# synth-zodiac-scorpio-kbd-mcu.net
KiCad netlist of a schematic drawn in EAGLE
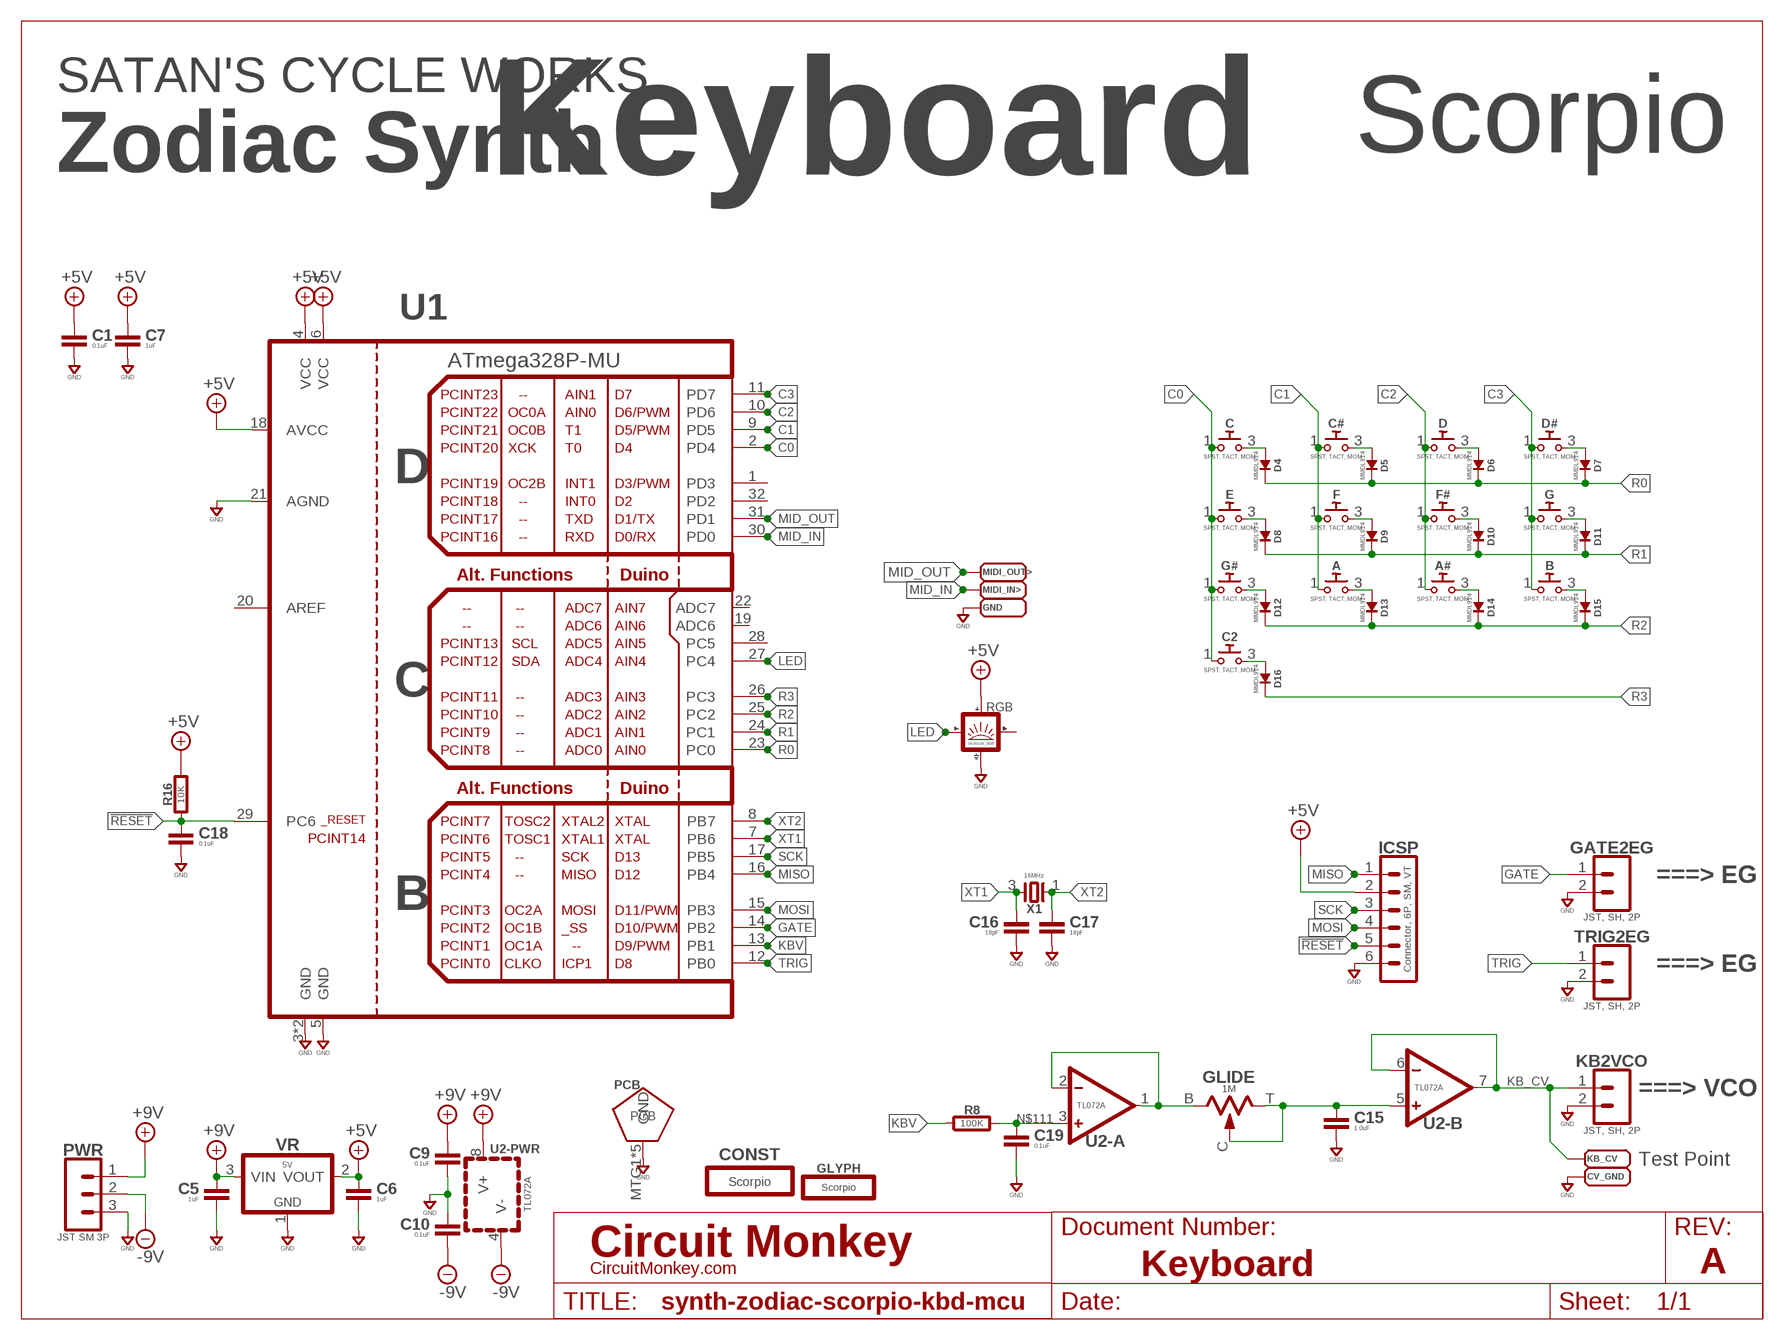
[diagram p0: schematic, sheet 1]

(export (version "E")
  (design (tool "Eeschema 10.0.6"))
  (components
    (comp (ref "A")
      (value "SPST, TACT, MOM")
      (footprint "eagle-import:B3FS-BACKMOUNT")
      (fields (field (name "MFR") "CK") (field (name "MPN") "B3FS"))
      (libsource (lib "eagle-import") (part "PUSHBTN-MOMB3FS-BLIND"))
    )
    (comp (ref "A#")
      (value "SPST, TACT, MOM")
      (footprint "eagle-import:B3FS-BACKMOUNT")
      (fields (field (name "MFR") "CK") (field (name "MPN") "B3FS"))
      (libsource (lib "eagle-import") (part "PUSHBTN-MOMB3FS-BLIND"))
    )
    (comp (ref "B")
      (value "SPST, TACT, MOM")
      (footprint "eagle-import:B3FS-BACKMOUNT")
      (fields (field (name "MFR") "CK") (field (name "MPN") "B3FS"))
      (libsource (lib "eagle-import") (part "PUSHBTN-MOMB3FS-BLIND"))
    )
    (comp (ref "C")
      (value "SPST, TACT, MOM")
      (footprint "eagle-import:B3FS-BACKMOUNT")
      (fields (field (name "MFR") "CK") (field (name "MPN") "B3FS"))
      (libsource (lib "eagle-import") (part "PUSHBTN-MOMB3FS-BLIND"))
    )
    (comp (ref "C#")
      (value "SPST, TACT, MOM")
      (footprint "eagle-import:B3FS-BACKMOUNT")
      (fields (field (name "MFR") "CK") (field (name "MPN") "B3FS"))
      (libsource (lib "eagle-import") (part "PUSHBTN-MOMB3FS-BLIND"))
    )
    (comp (ref "C1")
      (value "0.1uF")
      (footprint "eagle-import:0603-CAP")
      (libsource (lib "eagle-import") (part "CAPACITOR0603"))
    )
    (comp (ref "C2")
      (value "SPST, TACT, MOM")
      (footprint "eagle-import:B3FS-BACKMOUNT")
      (fields (field (name "MFR") "CK") (field (name "MPN") "B3FS"))
      (libsource (lib "eagle-import") (part "PUSHBTN-MOMB3FS-BLIND"))
    )
    (comp (ref "C5")
      (value "1uF")
      (footprint "eagle-import:0603-CAP")
      (libsource (lib "eagle-import") (part "CAPACITOR0603"))
    )
    (comp (ref "C6")
      (value "1uF")
      (footprint "eagle-import:0603-CAP")
      (libsource (lib "eagle-import") (part "CAPACITOR0603"))
    )
    (comp (ref "C7")
      (value "1uF")
      (footprint "eagle-import:0603-CAP")
      (libsource (lib "eagle-import") (part "CAPACITOR0603"))
    )
    (comp (ref "C9")
      (value "0.1uF")
      (footprint "eagle-import:0603-CAP")
      (libsource (lib "eagle-import") (part "CAPACITOR0603"))
    )
    (comp (ref "C10")
      (value "0.1uF")
      (footprint "eagle-import:0603-CAP")
      (libsource (lib "eagle-import") (part "CAPACITOR0603"))
    )
    (comp (ref "C15")
      (value "1.0uF")
      (footprint "eagle-import:0603-CAP")
      (libsource (lib "eagle-import") (part "CAPACITOR0603"))
    )
    (comp (ref "C16")
      (value "18pF")
      (footprint "eagle-import:0603-CAP")
      (libsource (lib "eagle-import") (part "CAPACITOR0603"))
    )
    (comp (ref "C17")
      (value "18pF")
      (footprint "eagle-import:0603-CAP")
      (libsource (lib "eagle-import") (part "CAPACITOR0603"))
    )
    (comp (ref "C18")
      (value "0.1uF")
      (footprint "eagle-import:0603-CAP")
      (libsource (lib "eagle-import") (part "CAPACITOR0603"))
    )
    (comp (ref "C19")
      (value "0.1uF")
      (footprint "eagle-import:0603-CAP")
      (libsource (lib "eagle-import") (part "CAPACITOR0603"))
    )
    (comp (ref "CONST")
      (value "Scorpio")
      (footprint "eagle-import:SCORPIO-CONST")
      (libsource (lib "eagle-import") (part "CONSTELLATION-SCORPIO"))
    )
    (comp (ref "CV_GND")
      (value "PAD-70X70SMD-070X070")
      (footprint "eagle-import:SMD-070MIL")
      (libsource (lib "eagle-import") (part "PAD-70X70SMD-070X070"))
    )
    (comp (ref "D")
      (value "SPST, TACT, MOM")
      (footprint "eagle-import:B3FS-BACKMOUNT")
      (fields (field (name "MFR") "CK") (field (name "MPN") "B3FS"))
      (libsource (lib "eagle-import") (part "PUSHBTN-MOMB3FS-BLIND"))
    )
    (comp (ref "D#")
      (value "SPST, TACT, MOM")
      (footprint "eagle-import:B3FS-BACKMOUNT")
      (fields (field (name "MFR") "CK") (field (name "MPN") "B3FS"))
      (libsource (lib "eagle-import") (part "PUSHBTN-MOMB3FS-BLIND"))
    )
    (comp (ref "D4")
      (value "MMDL914")
      (footprint "eagle-import:SOD-323")
      (fields (field (name "MFR") "ON Semi"))
      (libsource (lib "eagle-import") (part "DIODE-SWITCHING-SOD323"))
    )
    (comp (ref "D5")
      (value "MMDL914")
      (footprint "eagle-import:SOD-323")
      (fields (field (name "MFR") "ON Semi"))
      (libsource (lib "eagle-import") (part "DIODE-SWITCHING-SOD323"))
    )
    (comp (ref "D6")
      (value "MMDL914")
      (footprint "eagle-import:SOD-323")
      (fields (field (name "MFR") "ON Semi"))
      (libsource (lib "eagle-import") (part "DIODE-SWITCHING-SOD323"))
    )
    (comp (ref "D7")
      (value "MMDL914")
      (footprint "eagle-import:SOD-323")
      (fields (field (name "MFR") "ON Semi"))
      (libsource (lib "eagle-import") (part "DIODE-SWITCHING-SOD323"))
    )
    (comp (ref "D8")
      (value "MMDL914")
      (footprint "eagle-import:SOD-323")
      (fields (field (name "MFR") "ON Semi"))
      (libsource (lib "eagle-import") (part "DIODE-SWITCHING-SOD323"))
    )
    (comp (ref "D9")
      (value "MMDL914")
      (footprint "eagle-import:SOD-323")
      (fields (field (name "MFR") "ON Semi"))
      (libsource (lib "eagle-import") (part "DIODE-SWITCHING-SOD323"))
    )
    (comp (ref "D10")
      (value "MMDL914")
      (footprint "eagle-import:SOD-323")
      (fields (field (name "MFR") "ON Semi"))
      (libsource (lib "eagle-import") (part "DIODE-SWITCHING-SOD323"))
    )
    (comp (ref "D11")
      (value "MMDL914")
      (footprint "eagle-import:SOD-323")
      (fields (field (name "MFR") "ON Semi"))
      (libsource (lib "eagle-import") (part "DIODE-SWITCHING-SOD323"))
    )
    (comp (ref "D12")
      (value "MMDL914")
      (footprint "eagle-import:SOD-323")
      (fields (field (name "MFR") "ON Semi"))
      (libsource (lib "eagle-import") (part "DIODE-SWITCHING-SOD323"))
    )
    (comp (ref "D13")
      (value "MMDL914")
      (footprint "eagle-import:SOD-323")
      (fields (field (name "MFR") "ON Semi"))
      (libsource (lib "eagle-import") (part "DIODE-SWITCHING-SOD323"))
    )
    (comp (ref "D14")
      (value "MMDL914")
      (footprint "eagle-import:SOD-323")
      (fields (field (name "MFR") "ON Semi"))
      (libsource (lib "eagle-import") (part "DIODE-SWITCHING-SOD323"))
    )
    (comp (ref "D15")
      (value "MMDL914")
      (footprint "eagle-import:SOD-323")
      (fields (field (name "MFR") "ON Semi"))
      (libsource (lib "eagle-import") (part "DIODE-SWITCHING-SOD323"))
    )
    (comp (ref "D16")
      (value "MMDL914")
      (footprint "eagle-import:SOD-323")
      (fields (field (name "MFR") "ON Semi"))
      (libsource (lib "eagle-import") (part "DIODE-SWITCHING-SOD323"))
    )
    (comp (ref "E")
      (value "SPST, TACT, MOM")
      (footprint "eagle-import:B3FS-BACKMOUNT")
      (fields (field (name "MFR") "CK") (field (name "MPN") "B3FS"))
      (libsource (lib "eagle-import") (part "PUSHBTN-MOMB3FS-BLIND"))
    )
    (comp (ref "F")
      (value "SPST, TACT, MOM")
      (footprint "eagle-import:B3FS-BACKMOUNT")
      (fields (field (name "MFR") "CK") (field (name "MPN") "B3FS"))
      (libsource (lib "eagle-import") (part "PUSHBTN-MOMB3FS-BLIND"))
    )
    (comp (ref "F#")
      (value "SPST, TACT, MOM")
      (footprint "eagle-import:B3FS-BACKMOUNT")
      (fields (field (name "MFR") "CK") (field (name "MPN") "B3FS"))
      (libsource (lib "eagle-import") (part "PUSHBTN-MOMB3FS-BLIND"))
    )
    (comp (ref "G")
      (value "SPST, TACT, MOM")
      (footprint "eagle-import:B3FS-BACKMOUNT")
      (fields (field (name "MFR") "CK") (field (name "MPN") "B3FS"))
      (libsource (lib "eagle-import") (part "PUSHBTN-MOMB3FS-BLIND"))
    )
    (comp (ref "G#")
      (value "SPST, TACT, MOM")
      (footprint "eagle-import:B3FS-BACKMOUNT")
      (fields (field (name "MFR") "CK") (field (name "MPN") "B3FS"))
      (libsource (lib "eagle-import") (part "PUSHBTN-MOMB3FS-BLIND"))
    )
    (comp (ref "GATE2EG")
      (value "JST, SH, 2P")
      (footprint "eagle-import:BM02B-SRSS-TB")
      (fields (field (name "MFR") "JST") (field (name "MPN") "BMB02B-SRSS-TB"))
      (libsource (lib "eagle-import") (part "02P-SM-VT-SMT"))
    )
    (comp (ref "GLIDE")
      (value "1M")
      (footprint "eagle-import:POT-RV9110")
      (fields (field (name "MFR") "Tayda") (field (name "MPN") "RV9110NO-OS15A00"))
      (libsource (lib "eagle-import") (part "TRIMPOT9MM_PCB_SHAFT"))
    )
    (comp (ref "GLYPH")
      (value "Scorpio")
      (footprint "eagle-import:SCORPIO-GLYPH")
      (libsource (lib "eagle-import") (part "GLYPH-SCORPIO"))
    )
    (comp (ref "GND")
      (value "PAD-70X70SMD-070X070")
      (footprint "eagle-import:SMD-070MIL")
      (libsource (lib "eagle-import") (part "PAD-70X70SMD-070X070"))
    )
    (comp (ref "ICSP")
      (value "Connector, 6P, SM, VT")
      (footprint "eagle-import:BM06B-SRSS-TB")
      (fields (field (name "MFR") "JST") (field (name "MPN") "BM06-SRSS-TB"))
      (libsource (lib "eagle-import") (part "06P-SM-VT-SMT"))
    )
    (comp (ref "KB2VCO")
      (value "JST, SH, 2P")
      (footprint "eagle-import:BM02B-SRSS-TB")
      (fields (field (name "MFR") "JST") (field (name "MPN") "BMB02B-SRSS-TB"))
      (libsource (lib "eagle-import") (part "02P-SM-VT-SMT"))
    )
    (comp (ref "KB_CV")
      (value "PAD-70X70SMD-070X070")
      (footprint "eagle-import:SMD-070MIL")
      (libsource (lib "eagle-import") (part "PAD-70X70SMD-070X070"))
    )
    (comp (ref "MIDI_IN>")
      (value "PAD-70X70SMD-070X070")
      (footprint "eagle-import:SMD-070MIL")
      (libsource (lib "eagle-import") (part "PAD-70X70SMD-070X070"))
    )
    (comp (ref "MIDI_OUT>")
      (value "PAD-70X70SMD-070X070")
      (footprint "eagle-import:SMD-070MIL")
      (libsource (lib "eagle-import") (part "PAD-70X70SMD-070X070"))
    )
    (comp (ref "PCB")
      (value "PCB FAB")
      (footprint "eagle-import:PENTAGON-40MM-RAD")
      (libsource (lib "eagle-import") (part "PENTAGON-40R"))
    )
    (comp (ref "PWR")
      (value "JST SM 3P")
      (footprint "eagle-import:BM03B-SRSS-TB")
      (fields (field (name "MFR") "JST") (field (name "MPN") "BM03B-SRSS-TB"))
      (libsource (lib "eagle-import") (part "03P-SM-VT-SMT"))
    )
    (comp (ref "R8")
      (value "100K")
      (footprint "eagle-import:0603-RES")
      (libsource (lib "eagle-import") (part "RESISTOR0603"))
    )
    (comp (ref "R16")
      (value "10K")
      (footprint "eagle-import:0603-RES")
      (libsource (lib "eagle-import") (part "RESISTOR0603"))
    )
    (comp (ref "RGB")
      (value "SK2812B_3535")
      (footprint "eagle-import:SMD_3535")
      (libsource (lib "eagle-import") (part "SMART_LED3535"))
    )
    (comp (ref "TRIG2EG")
      (value "JST, SH, 2P")
      (footprint "eagle-import:BM02B-SRSS-TB")
      (fields (field (name "MFR") "JST") (field (name "MPN") "BMB02B-SRSS-TB"))
      (libsource (lib "eagle-import") (part "02P-SM-VT-SMT"))
    )
    (comp (ref "U1")
      (value "ATmega328P-MU")
      (footprint "eagle-import:MLF32")
      (fields (field (name "MFR") "Atmel") (field (name "MPN") "atmega328p-mu"))
      (libsource (lib "eagle-import") (part "ATMEGA328MU"))
    )
    (comp (ref "U2")
      (value "TL072A")
      (footprint "eagle-import:SOP08")
      (fields (field (name "MFR") "ST"))
      (libsource (lib "eagle-import") (part "DUALTL072A"))
    )
    (comp (ref "VR")
      (value "5V")
      (footprint "eagle-import:SOT-23")
      (fields (field (name "MFR") "Diodes, Inc.") (field (name "MPN") "AP7387-50SA"))
      (libsource (lib "eagle-import") (part "LDO-3P--5V-SOT23"))
    )
    (comp (ref "X1")
      (value "16MHz")
      (footprint "eagle-import:32X25")
      (fields (field (name "MFR") "Epson") (field (name "MPN") "FA-238 16.0000MB-K3"))
      (libsource (lib "eagle-import") (part "2P3.2X2.5"))
    )
  )
  (nets
    (net (code "1") (name "+5V") (class "Default")
      (node (ref "C1") (pin "1") (pinfunction "1_1") (pintype "passive"))
      (node (ref "C6") (pin "1") (pinfunction "1_1") (pintype "passive"))
      (node (ref "C7") (pin "1") (pinfunction "1_1") (pintype "passive"))
      (node (ref "ICSP") (pin "2") (pinfunction "2_2") (pintype "passive"))
      (node (ref "R16") (pin "2") (pinfunction "2_2") (pintype "passive"))
      (node (ref "RGB") (pin "4") (pinfunction "VDD_4") (pintype "bidirectional"))
      (node (ref "U1") (pin "18") (pinfunction "AVCC_18") (pintype "power_in"))
      (node (ref "U1") (pin "4") (pinfunction "VCC_4") (pintype "power_in"))
      (node (ref "U1") (pin "6") (pinfunction "VCC_6") (pintype "power_in"))
      (node (ref "VR") (pin "2") (pinfunction "VOUT_2") (pintype "power_in"))
    )
    (net (code "2") (name "+9V") (class "Default")
      (node (ref "C5") (pin "1") (pinfunction "1_1") (pintype "passive"))
      (node (ref "C9") (pin "1") (pinfunction "1_1") (pintype "passive"))
      (node (ref "PWR") (pin "1") (pinfunction "1_1") (pintype "passive"))
      (node (ref "U2") (pin "8") (pinfunction "V+_8") (pintype "power_in"))
      (node (ref "VR") (pin "3") (pinfunction "VIN_3") (pintype "power_in"))
    )
    (net (code "3") (name "-9V") (class "Default")
      (node (ref "C10") (pin "2") (pinfunction "2_2") (pintype "passive"))
      (node (ref "PWR") (pin "2") (pinfunction "2_2") (pintype "passive"))
      (node (ref "U2") (pin "4") (pinfunction "V-_4") (pintype "power_in"))
    )
    (net (code "4") (name "/KB_CV") (class "Default")
      (node (ref "KB2VCO") (pin "1") (pinfunction "1_1") (pintype "passive"))
      (node (ref "KB_CV") (pin "1") (pinfunction "PAD_1") (pintype "bidirectional"))
      (node (ref "U2") (pin "6") (pinfunction "-_6") (pintype "input"))
      (node (ref "U2") (pin "7") (pinfunction "OUT_7") (pintype "output"))
    )
    (net (code "5") (name "/N$111") (class "Default")
      (node (ref "C19") (pin "1") (pinfunction "1_1") (pintype "passive"))
      (node (ref "R8") (pin "2") (pinfunction "2_2") (pintype "passive"))
      (node (ref "U2") (pin "3") (pinfunction "+_3") (pintype "input"))
    )
    (net (code "6") (name "/~{RESET}") (class "Default")
      (node (ref "C18") (pin "1") (pinfunction "1_1") (pintype "passive"))
      (node (ref "ICSP") (pin "5") (pinfunction "5_5") (pintype "passive"))
      (node (ref "R16") (pin "1") (pinfunction "1_1") (pintype "passive"))
      (node (ref "U1") (pin "29") (pinfunction "PC6_29") (pintype "bidirectional"))
    )
    (net (code "7") (name "C0") (class "Default")
      (node (ref "C") (pin "1") (pinfunction "1_1") (pintype "passive"))
      (node (ref "C2") (pin "1") (pinfunction "1_1") (pintype "passive"))
      (node (ref "E") (pin "1") (pinfunction "1_1") (pintype "passive"))
      (node (ref "G#") (pin "1") (pinfunction "1_1") (pintype "passive"))
      (node (ref "U1") (pin "2") (pinfunction "PD4_2") (pintype "bidirectional"))
    )
    (net (code "8") (name "C1") (class "Default")
      (node (ref "A") (pin "1") (pinfunction "1_1") (pintype "passive"))
      (node (ref "C#") (pin "1") (pinfunction "1_1") (pintype "passive"))
      (node (ref "F") (pin "1") (pinfunction "1_1") (pintype "passive"))
      (node (ref "U1") (pin "9") (pinfunction "PD5_9") (pintype "bidirectional"))
    )
    (net (code "9") (name "C2") (class "Default")
      (node (ref "A#") (pin "1") (pinfunction "1_1") (pintype "passive"))
      (node (ref "D") (pin "1") (pinfunction "1_1") (pintype "passive"))
      (node (ref "F#") (pin "1") (pinfunction "1_1") (pintype "passive"))
      (node (ref "U1") (pin "10") (pinfunction "PD6_10") (pintype "bidirectional"))
    )
    (net (code "10") (name "C3") (class "Default")
      (node (ref "B") (pin "1") (pinfunction "1_1") (pintype "passive"))
      (node (ref "D#") (pin "1") (pinfunction "1_1") (pintype "passive"))
      (node (ref "G") (pin "1") (pinfunction "1_1") (pintype "passive"))
      (node (ref "U1") (pin "11") (pinfunction "PD7_11") (pintype "bidirectional"))
    )
    (net (code "11") (name "GATE") (class "Default")
      (node (ref "GATE2EG") (pin "1") (pinfunction "1_1") (pintype "passive"))
      (node (ref "U1") (pin "14") (pinfunction "PB2_14") (pintype "bidirectional"))
    )
    (net (code "12") (name "GND") (class "Default")
      (node (ref "C1") (pin "2") (pinfunction "2_2") (pintype "passive"))
      (node (ref "C10") (pin "1") (pinfunction "1_1") (pintype "passive"))
      (node (ref "C15") (pin "2") (pinfunction "2_2") (pintype "passive"))
      (node (ref "C16") (pin "2") (pinfunction "2_2") (pintype "passive"))
      (node (ref "C17") (pin "2") (pinfunction "2_2") (pintype "passive"))
      (node (ref "C18") (pin "2") (pinfunction "2_2") (pintype "passive"))
      (node (ref "C19") (pin "2") (pinfunction "2_2") (pintype "passive"))
      (node (ref "C5") (pin "2") (pinfunction "2_2") (pintype "passive"))
      (node (ref "C6") (pin "2") (pinfunction "2_2") (pintype "passive"))
      (node (ref "C7") (pin "2") (pinfunction "2_2") (pintype "passive"))
      (node (ref "C9") (pin "2") (pinfunction "2_2") (pintype "passive"))
      (node (ref "CV_GND") (pin "1") (pinfunction "PAD_1") (pintype "bidirectional"))
      (node (ref "GATE2EG") (pin "2") (pinfunction "2_2") (pintype "passive"))
      (node (ref "GND") (pin "1") (pinfunction "PAD_1") (pintype "bidirectional"))
      (node (ref "ICSP") (pin "6") (pinfunction "6_6") (pintype "passive"))
      (node (ref "KB2VCO") (pin "2") (pinfunction "2_2") (pintype "passive"))
      (node (ref "PCB") (pin "MTG1") (pinfunction "GND_MTG1") (pintype "bidirectional"))
      (node (ref "PCB") (pin "MTG2") (pinfunction "GND_MTG2") (pintype "bidirectional"))
      (node (ref "PCB") (pin "MTG3") (pinfunction "GND_MTG3") (pintype "bidirectional"))
      (node (ref "PCB") (pin "MTG4") (pinfunction "GND_MTG4") (pintype "bidirectional"))
      (node (ref "PCB") (pin "MTG5") (pinfunction "GND_MTG5") (pintype "bidirectional"))
      (node (ref "PWR") (pin "3") (pinfunction "3_3") (pintype "passive"))
      (node (ref "RGB") (pin "2") (pinfunction "GND_2") (pintype "bidirectional"))
      (node (ref "TRIG2EG") (pin "2") (pinfunction "2_2") (pintype "passive"))
      (node (ref "U1") (pin "21") (pinfunction "AGND_21") (pintype "power_in"))
      (node (ref "U1") (pin "3") (pinfunction "GND_3") (pintype "power_in"))
      (node (ref "U1") (pin "5") (pinfunction "GND_5") (pintype "power_in"))
      (node (ref "U1") (pin "PAD") (pinfunction "GND_PAD") (pintype "power_in"))
      (node (ref "VR") (pin "1") (pinfunction "GND_1") (pintype "power_in"))
    )
    (net (code "13") (name "KBV") (class "Default")
      (node (ref "R8") (pin "1") (pinfunction "1_1") (pintype "passive"))
      (node (ref "U1") (pin "13") (pinfunction "PB1_13") (pintype "bidirectional"))
    )
    (net (code "14") (name "LED") (class "Default")
      (node (ref "RGB") (pin "3") (pinfunction "IN_3") (pintype "bidirectional"))
      (node (ref "U1") (pin "27") (pinfunction "PC4_27") (pintype "bidirectional"))
    )
    (net (code "15") (name "MID_IN") (class "Default")
      (node (ref "MIDI_IN>") (pin "1") (pinfunction "PAD_1") (pintype "bidirectional"))
      (node (ref "U1") (pin "30") (pinfunction "PD0_30") (pintype "bidirectional"))
    )
    (net (code "16") (name "MID_OUT") (class "Default")
      (node (ref "MIDI_OUT>") (pin "1") (pinfunction "PAD_1") (pintype "bidirectional"))
      (node (ref "U1") (pin "31") (pinfunction "PD1_31") (pintype "bidirectional"))
    )
    (net (code "17") (name "MISO") (class "Default")
      (node (ref "ICSP") (pin "1") (pinfunction "1_1") (pintype "passive"))
      (node (ref "U1") (pin "16") (pinfunction "PB4_16") (pintype "bidirectional"))
    )
    (net (code "18") (name "MOSI") (class "Default")
      (node (ref "ICSP") (pin "4") (pinfunction "4_4") (pintype "passive"))
      (node (ref "U1") (pin "15") (pinfunction "PB3_15") (pintype "bidirectional"))
    )
    (net (code "19") (name "Net-(A#-2)") (class "Default")
      (node (ref "A#") (pin "3") (pinfunction "2_3") (pintype "passive"))
      (node (ref "D14") (pin "A") (pinfunction "A_A") (pintype "passive"))
    )
    (net (code "20") (name "Net-(A-2)") (class "Default")
      (node (ref "A") (pin "3") (pinfunction "2_3") (pintype "passive"))
      (node (ref "D13") (pin "A") (pinfunction "A_A") (pintype "passive"))
    )
    (net (code "21") (name "Net-(B-2)") (class "Default")
      (node (ref "B") (pin "3") (pinfunction "2_3") (pintype "passive"))
      (node (ref "D15") (pin "A") (pinfunction "A_A") (pintype "passive"))
    )
    (net (code "22") (name "Net-(C#-2)") (class "Default")
      (node (ref "C#") (pin "3") (pinfunction "2_3") (pintype "passive"))
      (node (ref "D5") (pin "A") (pinfunction "A_A") (pintype "passive"))
    )
    (net (code "23") (name "Net-(C-2)") (class "Default")
      (node (ref "C") (pin "3") (pinfunction "2_3") (pintype "passive"))
      (node (ref "D4") (pin "A") (pinfunction "A_A") (pintype "passive"))
    )
    (net (code "24") (name "Net-(C2-2)") (class "Default")
      (node (ref "C2") (pin "3") (pinfunction "2_3") (pintype "passive"))
      (node (ref "D16") (pin "A") (pinfunction "A_A") (pintype "passive"))
    )
    (net (code "25") (name "Net-(D#-2)") (class "Default")
      (node (ref "D#") (pin "3") (pinfunction "2_3") (pintype "passive"))
      (node (ref "D7") (pin "A") (pinfunction "A_A") (pintype "passive"))
    )
    (net (code "26") (name "Net-(D-2)") (class "Default")
      (node (ref "D") (pin "3") (pinfunction "2_3") (pintype "passive"))
      (node (ref "D6") (pin "A") (pinfunction "A_A") (pintype "passive"))
    )
    (net (code "27") (name "Net-(E-2)") (class "Default")
      (node (ref "D8") (pin "A") (pinfunction "A_A") (pintype "passive"))
      (node (ref "E") (pin "3") (pinfunction "2_3") (pintype "passive"))
    )
    (net (code "28") (name "Net-(F#-2)") (class "Default")
      (node (ref "D10") (pin "A") (pinfunction "A_A") (pintype "passive"))
      (node (ref "F#") (pin "3") (pinfunction "2_3") (pintype "passive"))
    )
    (net (code "29") (name "Net-(F-2)") (class "Default")
      (node (ref "D9") (pin "A") (pinfunction "A_A") (pintype "passive"))
      (node (ref "F") (pin "3") (pinfunction "2_3") (pintype "passive"))
    )
    (net (code "30") (name "Net-(G#-2)") (class "Default")
      (node (ref "D12") (pin "A") (pinfunction "A_A") (pintype "passive"))
      (node (ref "G#") (pin "3") (pinfunction "2_3") (pintype "passive"))
    )
    (net (code "31") (name "Net-(G-2)") (class "Default")
      (node (ref "D11") (pin "A") (pinfunction "A_A") (pintype "passive"))
      (node (ref "G") (pin "3") (pinfunction "2_3") (pintype "passive"))
    )
    (net (code "32") (name "Net-(GLIDE-1)") (class "Default")
      (node (ref "GLIDE") (pin "B") (pinfunction "1_B") (pintype "passive"))
      (node (ref "U2") (pin "1") (pinfunction "OUT_1") (pintype "output"))
      (node (ref "U2") (pin "2") (pinfunction "-_2") (pintype "input"))
    )
    (net (code "33") (name "Net-(GLIDE-2)") (class "Default")
      (node (ref "C15") (pin "1") (pinfunction "1_1") (pintype "passive"))
      (node (ref "GLIDE") (pin "C") (pinfunction "2_C") (pintype "passive"))
      (node (ref "GLIDE") (pin "T") (pinfunction "3_T") (pintype "passive"))
      (node (ref "U2") (pin "5") (pinfunction "+_5") (pintype "input"))
    )
    (net (code "34") (name "R0") (class "Default")
      (node (ref "D4") (pin "K") (pinfunction "K_K") (pintype "passive"))
      (node (ref "D5") (pin "K") (pinfunction "K_K") (pintype "passive"))
      (node (ref "D6") (pin "K") (pinfunction "K_K") (pintype "passive"))
      (node (ref "D7") (pin "K") (pinfunction "K_K") (pintype "passive"))
      (node (ref "U1") (pin "23") (pinfunction "PC0_23") (pintype "bidirectional"))
    )
    (net (code "35") (name "R1") (class "Default")
      (node (ref "D10") (pin "K") (pinfunction "K_K") (pintype "passive"))
      (node (ref "D11") (pin "K") (pinfunction "K_K") (pintype "passive"))
      (node (ref "D8") (pin "K") (pinfunction "K_K") (pintype "passive"))
      (node (ref "D9") (pin "K") (pinfunction "K_K") (pintype "passive"))
      (node (ref "U1") (pin "24") (pinfunction "PC1_24") (pintype "bidirectional"))
    )
    (net (code "36") (name "R2") (class "Default")
      (node (ref "D12") (pin "K") (pinfunction "K_K") (pintype "passive"))
      (node (ref "D13") (pin "K") (pinfunction "K_K") (pintype "passive"))
      (node (ref "D14") (pin "K") (pinfunction "K_K") (pintype "passive"))
      (node (ref "D15") (pin "K") (pinfunction "K_K") (pintype "passive"))
      (node (ref "U1") (pin "25") (pinfunction "PC2_25") (pintype "bidirectional"))
    )
    (net (code "37") (name "R3") (class "Default")
      (node (ref "D16") (pin "K") (pinfunction "K_K") (pintype "passive"))
      (node (ref "U1") (pin "26") (pinfunction "PC3_26") (pintype "bidirectional"))
    )
    (net (code "38") (name "SCK") (class "Default")
      (node (ref "ICSP") (pin "3") (pinfunction "3_3") (pintype "passive"))
      (node (ref "U1") (pin "17") (pinfunction "PB5_17") (pintype "bidirectional"))
    )
    (net (code "39") (name "TRIG") (class "Default")
      (node (ref "TRIG2EG") (pin "1") (pinfunction "1_1") (pintype "passive"))
      (node (ref "U1") (pin "12") (pinfunction "PB0_12") (pintype "bidirectional"))
    )
    (net (code "40") (name "XT1") (class "Default")
      (node (ref "C16") (pin "1") (pinfunction "1_1") (pintype "passive"))
      (node (ref "U1") (pin "7") (pinfunction "PB6_7") (pintype "bidirectional"))
      (node (ref "X1") (pin "3") (pinfunction "P$2_3") (pintype "passive"))
    )
    (net (code "41") (name "XT2") (class "Default")
      (node (ref "C17") (pin "1") (pinfunction "1_1") (pintype "passive"))
      (node (ref "U1") (pin "8") (pinfunction "PB7_8") (pintype "bidirectional"))
      (node (ref "X1") (pin "1") (pinfunction "P$1_1") (pintype "passive"))
    )
    (net (code "42") (name "unconnected-(RGB-OUT-Pad1)") (class "Default")
      (node (ref "RGB") (pin "1") (pinfunction "OUT_1") (pintype "bidirectional"))
    )
    (net (code "43") (name "unconnected-(U1-ADC6-Pad19)") (class "Default")
      (node (ref "U1") (pin "19") (pinfunction "ADC6_19") (pintype "bidirectional"))
    )
    (net (code "44") (name "unconnected-(U1-ADC7-Pad22)") (class "Default")
      (node (ref "U1") (pin "22") (pinfunction "ADC7_22") (pintype "bidirectional"))
    )
    (net (code "45") (name "unconnected-(U1-AREF-Pad20)") (class "Default")
      (node (ref "U1") (pin "20") (pinfunction "AREF_20") (pintype "input"))
    )
    (net (code "46") (name "unconnected-(U1-PC5-Pad28)") (class "Default")
      (node (ref "U1") (pin "28") (pinfunction "PC5_28") (pintype "bidirectional"))
    )
    (net (code "47") (name "unconnected-(U1-PD2-Pad32)") (class "Default")
      (node (ref "U1") (pin "32") (pinfunction "PD2_32") (pintype "bidirectional"))
    )
    (net (code "48") (name "unconnected-(U1-PD3-Pad1)") (class "Default")
      (node (ref "U1") (pin "1") (pinfunction "PD3_1") (pintype "bidirectional"))
    )
  )
)
